# GNSS_GPS_IMU.net
KiCad netlist of a schematic drawn in Altium Designer
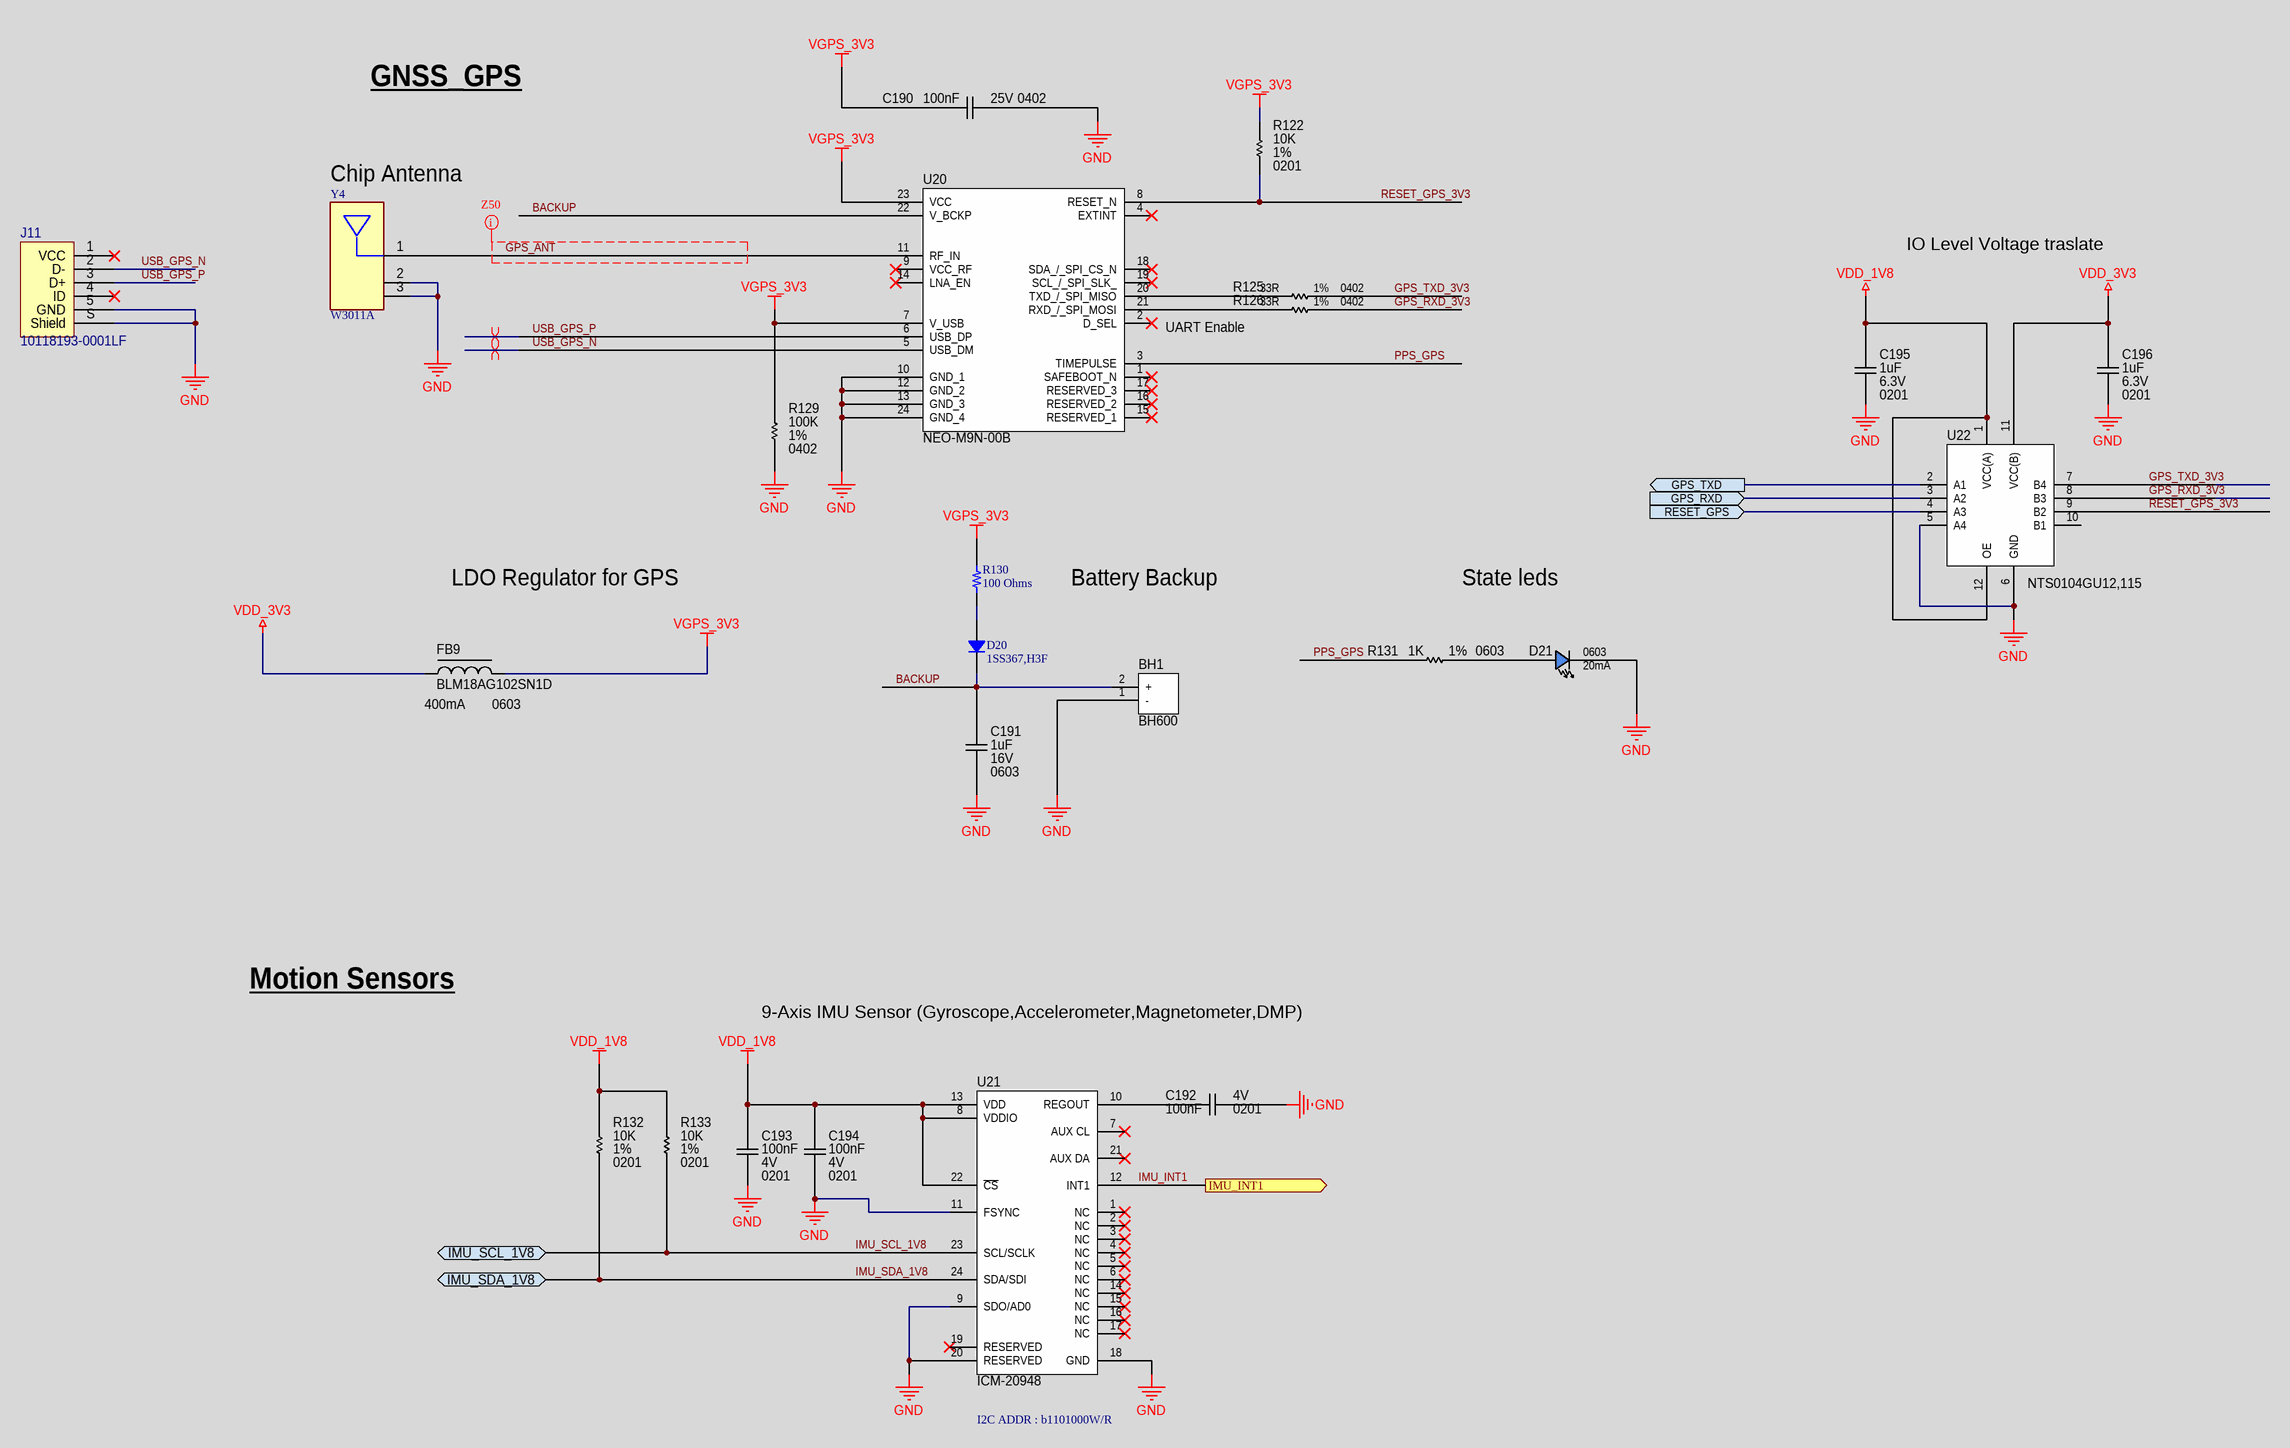
[diagram p0: GNSS_GPS_IMU.SchDoc]

(export (version "E")
  (design (tool "Eeschema 10.0.6"))
  (components
    (comp (ref "BH1")
      (value "BH600")
      (footprint "MECH_BATTERY_HOLDER_BH600")
      (description "Battery Holder 1 Cells Thermoplastic Tray")
      (fields (field (name "MANUFACTURER") "Memory Protection Devices"))
      (libsource (lib "Electronic Devices_LIB") (part "MECH_BATTERY_HOLDER_BH600"))
    )
    (comp (ref "C190")
      (value "CC0402KRX5R8BB104")
      (footprint "CAP_0402_CAPC1005X05N")
      (description "Multilayer Ceramic Capacitor, 0.1 uF, 25 V, ± 10%, X7R, 0402 [1005 Metric]")
      (fields
        (field (name "MANUFACTURER") "Yageo")
        (field (name "TOLERANCE") "10%")
        (field (name "CAPACITANCE") "100nF")
        (field (name "VOLTAGE RATING") "25V")
        (field (name "CASE/PACKAGE") "0402")
      )
      (libsource (lib "Electronic Devices_LIB") (part "CAP_100NF_25V_X7R_0402"))
    )
    (comp (ref "C191")
      (value "CL10A105KO8NNNC")
      (footprint "CAP_0603_CAPC1608X08N")
      (description "CAP CER 1UF 16V X5R 0603")
      (fields
        (field (name "MANUFACTURER") "Samsung")
        (field (name "TOLERANCE") "10%")
        (field (name "VOLTAGE RATING") "16V")
        (field (name "CAPACITANCE") "1uF")
        (field (name "CASE/PACKAGE") "0603")
      )
      (libsource (lib "Electronic Devices_LIB") (part "CAP_1UF_16V_X5R_0603"))
    )
    (comp (ref "C192")
      (value "C0201C104K7PAC7867")
      (footprint "CAP_0201_CAPC0603X03N")
      (description "SMD Comm X5R 0201 (0603Metric) ceramic capacitor 0.024Lx0.012W 0.60mmx0.30mm X5R ±10% 0.1muF")
      (fields
        (field (name "MANUFACTURER") "KEMET")
        (field (name "TOLERANCE") "10%")
        (field (name "VOLTAGE RATING") "4V")
        (field (name "CAPACITANCE") "100nF")
        (field (name "CASE/PACKAGE") "0201")
      )
      (libsource (lib "Electronic Devices_LIB") (part "CAP_100NF_4V_X5R_0201"))
    )
    (comp (ref "C193")
      (value "C0201C104K7PAC7867")
      (footprint "CAP_0201_CAPC0603X03N")
      (description "SMD Comm X5R 0201 (0603Metric) ceramic capacitor 0.024Lx0.012W 0.60mmx0.30mm X5R ±10% 0.1muF")
      (fields
        (field (name "MANUFACTURER") "KEMET")
        (field (name "TOLERANCE") "10%")
        (field (name "VOLTAGE RATING") "4V")
        (field (name "CAPACITANCE") "100nF")
        (field (name "CASE/PACKAGE") "0201")
      )
      (libsource (lib "Electronic Devices_LIB") (part "CAP_100NF_4V_X5R_0201"))
    )
    (comp (ref "C194")
      (value "C0201C104K7PAC7867")
      (footprint "CAP_0201_CAPC0603X03N")
      (description "SMD Comm X5R 0201 (0603Metric) ceramic capacitor 0.024Lx0.012W 0.60mmx0.30mm X5R ±10% 0.1muF")
      (fields
        (field (name "MANUFACTURER") "KEMET")
        (field (name "TOLERANCE") "10%")
        (field (name "VOLTAGE RATING") "4V")
        (field (name "CAPACITANCE") "100nF")
        (field (name "CASE/PACKAGE") "0201")
      )
      (libsource (lib "Electronic Devices_LIB") (part "CAP_100NF_4V_X5R_0201"))
    )
    (comp (ref "C195")
      (value "02016D105MAT2A")
      (footprint "CAP_0201_CAPC0603X03N")
      (description "0201 1 uF 6.3 V ±20 % Tolerance X5R Surface Mount Multilayer Ceramic Capacitor")
      (fields
        (field (name "MANUFACTURER") "Kyocera AVX")
        (field (name "TOLERANCE") "20%")
        (field (name "VOLTAGE RATING (DC)") "6.3V")
        (field (name "CAPACITANCE") "1uF")
        (field (name "CASE/PACKAGE") "0201")
      )
      (libsource (lib "Electronic Devices_LIB") (part "CAP_1UF_6.3V_X5R_0201"))
    )
    (comp (ref "C196")
      (value "02016D105MAT2A")
      (footprint "CAP_0201_CAPC0603X03N")
      (description "0201 1 uF 6.3 V ±20 % Tolerance X5R Surface Mount Multilayer Ceramic Capacitor")
      (fields
        (field (name "MANUFACTURER") "Kyocera AVX")
        (field (name "TOLERANCE") "20%")
        (field (name "VOLTAGE RATING (DC)") "6.3V")
        (field (name "CAPACITANCE") "1uF")
        (field (name "CASE/PACKAGE") "0201")
      )
      (libsource (lib "Electronic Devices_LIB") (part "CAP_1UF_6.3V_X5R_0201"))
    )
    (comp (ref "D20")
      (value "1SS367,H3F")
      (footprint "SOD323")
      (description "DIODE SCHOTTKY 10V 100MA USC")
      (fields (field (name "MANUFACTURER") "Toshiba Semiconductor and Storage"))
      (libsource (lib "Celestial Altium Library - altium_library") (part "Diode"))
    )
    (comp (ref "D21")
      (value "ASCKCB00-NS3T4010302")
      (footprint "LED_0603-BLUE-0.75mm")
      (description "LED Single Chip Blue 467nm 20mA 2-Pin DFN T/R")
      (fields
        (field (name "MANUFACTURER") "Broadcom")
        (field (name "CASE/PACKCAGE") "0603")
        (field (name "TEST CURRENT") "20mA")
      )
      (libsource (lib "Electronic Devices_LIB") (part "LED_DIO_BLUE_20mA_0603_ASCKCB00-NS3T4010302"))
    )
    (comp (ref "FB9")
      (value "BLM18AG102SN1D")
      (footprint "IND_0603_INDC1608X08N")
      (description "Ferrite Beads Multi-Layer 1KOhm 25% 100MHz 450mA 500mOhm DCR 0603 T/R")
      (fields
        (field (name "MANUFACTURER") "Murata")
        (field (name "TOLERANCE") "25%")
        (field (name "MAX DC CURRENT") "400mA")
        (field (name "CASE/PACKAGE") "0603")
      )
      (libsource (lib "Electronic Devices_LIB") (part "IND_FERRITA_1K_450mA_BLM18AG102SN1D"))
    )
    (comp (ref "J11")
      (value "10118193-0001LF")
      (footprint "FCI USB 10118193-0001LF")
      (description "CONN RCPT USB2.0 MICRO B SMD R/A")
      (fields (field (name "MANUFACTURER") "Amphenol ICC (FCI)"))
      (libsource (lib "Celestial Altium Library - altium_library") (part "USB 2.0 Type B Micro"))
    )
    (comp (ref "R122")
      (value "RC0201FR-0710KL")
      (footprint "RES_0201_RESC0603X02N")
      (description "SMD Chip Resistor, 10 kOhm, ± 1%, 50 mW, 0201 [0603 Metric], Thick Film, General Purpose")
      (fields
        (field (name "MANUFACTURER") "Yageo")
        (field (name "TOLERANCE") "1%")
        (field (name "RESISTANCE") "10K")
        (field (name "CASE CODE (IMPERIAL)") "0201")
      )
      (libsource (lib "Electronic Devices_LIB") (part "RES_10K_1/12W_1%_0201"))
    )
    (comp (ref "R125")
      (value "RC0402FR-0733RL")
      (footprint "RES_0402_RESC1005X04N")
      (description "SMD Chip Resistor, 33 Ohm, ± 1%, 62.5 mW, 0402 [1005 Metric], Thick Film, General Purpose")
      (fields
        (field (name "MANUFACTURER") "Yageo")
        (field (name "TOLERANCE") "1%")
        (field (name "RESISTANCE") "33R")
        (field (name "CASE/PACKAGE") "0402")
      )
      (libsource (lib "Electronic Devices_LIB") (part "RES_33R_1%_62.5mW_0402"))
    )
    (comp (ref "R126")
      (value "RC0402FR-0733RL")
      (footprint "RES_0402_RESC1005X04N")
      (description "SMD Chip Resistor, 33 Ohm, ± 1%, 62.5 mW, 0402 [1005 Metric], Thick Film, General Purpose")
      (fields
        (field (name "MANUFACTURER") "Yageo")
        (field (name "TOLERANCE") "1%")
        (field (name "RESISTANCE") "33R")
        (field (name "CASE/PACKAGE") "0402")
      )
      (libsource (lib "Electronic Devices_LIB") (part "RES_33R_1%_62.5mW_0402"))
    )
    (comp (ref "R129")
      (value "RC0402FR-07100KL")
      (footprint "RES_0402_RESC1005X04N")
      (description "SMD Chip Resistor, 100 kOhm, ± 1%, 63 mW, 0402 [1005 Metric], Thick Film, General Purpose")
      (fields
        (field (name "MANUFACTURER") "Yageo")
        (field (name "RESISTANCE") "100K")
        (field (name "TOLERANCE") "1%")
        (field (name "CASE/PACKAGE") "0402")
      )
      (libsource (lib "Electronic Devices_LIB") (part "RES_100K_1%_100mW_0402"))
    )
    (comp (ref "R130")
      (value "100 Ohms")
      (footprint "RES 0402_1005")
      (description "RES 100 OHM 1% 1/16W 0402")
      (fields
        (field (name "PART NUMBER") "RMCF0402FT100R")
        (field (name "MANUFACTURER") "Stackpole Electronics Inc")
      )
      (libsource (lib "Celestial Altium Library - altium_library") (part "Resistor"))
    )
    (comp (ref "R131")
      (value "AC0603FR-101KL")
      (footprint "RES_0603_RESC1608X04N")
      (description "Chip Resistor Automotive Grade Thick Film 0603 1kOhm 1% Paper T/R")
      (fields
        (field (name "MANUFACTURER") "Yageo")
        (field (name "RESISTANCE") "1K")
        (field (name "TOLERANCE") "1%")
        (field (name "CASE/PACKAGE") "0603")
      )
      (libsource (lib "Electronic Devices_LIB") (part "RES_1K_1%_100mW_0603"))
    )
    (comp (ref "R132")
      (value "RC0201FR-0710KL")
      (footprint "RES_0201_RESC0603X02N")
      (description "SMD Chip Resistor, 10 kOhm, ± 1%, 50 mW, 0201 [0603 Metric], Thick Film, General Purpose")
      (fields
        (field (name "MANUFACTURER") "Yageo")
        (field (name "TOLERANCE") "1%")
        (field (name "RESISTANCE") "10K")
        (field (name "CASE CODE (IMPERIAL)") "0201")
      )
      (libsource (lib "Electronic Devices_LIB") (part "RES_10K_1/12W_1%_0201"))
    )
    (comp (ref "R133")
      (value "RC0201FR-0710KL")
      (footprint "RES_0201_RESC0603X02N")
      (description "SMD Chip Resistor, 10 kOhm, ± 1%, 50 mW, 0201 [0603 Metric], Thick Film, General Purpose")
      (fields
        (field (name "MANUFACTURER") "Yageo")
        (field (name "TOLERANCE") "1%")
        (field (name "RESISTANCE") "10K")
        (field (name "CASE CODE (IMPERIAL)") "0201")
      )
      (libsource (lib "Electronic Devices_LIB") (part "RES_10K_1/12W_1%_0201"))
    )
    (comp (ref "U20")
      (value "NEO-M9N-00B")
      (footprint "IC_MODULE_UBLOX_NEOM9N00B")
      (description "GNSS module, Flash, TCXO, SAW, LNA, LCC, 12x16 mm Professional Grade")
      (fields (field (name "MANUFACTURER") "u-blox"))
      (libsource (lib "Electronic Devices_LIB") (part "IC_MODULE_UBLOX_NEO-M9N-00B"))
    )
    (comp (ref "U21")
      (value "ICM-20948")
      (footprint "IC_IMU_TDK_InvenSense_0_IPC_A")
      (description "IMU (Inertial Measurement Unit), 9-Axis, Accelerometer, Gyroscope, Compass")
      (fields (field (name "MANUFACTURER") "TDK"))
      (libsource (lib "Electronic Devices_LIB") (part "IC_IMU_9AXIS_ICM-20948"))
    )
    (comp (ref "U22")
      (value "NTS0104GU12,115")
      (footprint "IC_LEVEL_TRASLATOR_XQFN12_0P4_1P8X2P1")
      (description "NTS0104 Series 50 Mbps Dual Supply 3-ST O-DRN Translating Transceiver- XQFN-12")
      (fields (field (name "MANUFACTURER") "NXP Semiconductors"))
      (libsource (lib "Electronic Devices_LIB") (part "IC_LEVEL_TRASLATOR_NTS0104GU12,115"))
    )
    (comp (ref "Y4")
      (value "W3011A")
      (footprint "FP-W3011A-MFG")
      (description "RF ANT 1.575GHZ CHIP SOLDER SMD")
      (fields
        (field (name "OCTOPART") "https://octopart.com/w3011a-pulse-10684180")
        (field (name "MANUFACTURER") "PulseLarsen Antennas")
      )
      (libsource (lib "Altium Content Vault") (part "6d32a7a60510b62759eb526d3a7a656"))
    )
  )
  (nets
    (net (code "1") (name "/BACKUP") (class "Default")
      (node (ref "BH1") (pin "2") (pinfunction "+_2") (pintype "passive"))
      (node (ref "C191") (pin "2") (pinfunction "2_2") (pintype "passive"))
      (node (ref "D20") (pin "2") (pinfunction "2_2") (pintype "passive"))
      (node (ref "U20") (pin "22") (pinfunction "V_BCKP_22") (pintype "passive"))
    )
    (net (code "2") (name "/GPS_ANT") (class "Default")
      (node (ref "U20") (pin "11") (pinfunction "RF_IN_11") (pintype "passive"))
      (node (ref "Y4") (pin "1") (pinfunction "Feed_1") (pintype "power_in"))
    )
    (net (code "3") (name "/GPS_RXD") (class "Default")
      (node (ref "U22") (pin "3") (pinfunction "A2_3") (pintype "passive"))
    )
    (net (code "4") (name "/GPS_RXD_3V3") (class "Default")
      (node (ref "R126") (pin "2") (pinfunction "2_2") (pintype "passive"))
      (node (ref "U22") (pin "8") (pinfunction "B3_8") (pintype "passive"))
    )
    (net (code "5") (name "/GPS_TXD") (class "Default")
      (node (ref "U22") (pin "2") (pinfunction "A1_2") (pintype "passive"))
    )
    (net (code "6") (name "/GPS_TXD_3V3") (class "Default")
      (node (ref "R125") (pin "2") (pinfunction "2_2") (pintype "passive"))
      (node (ref "U22") (pin "7") (pinfunction "B4_7") (pintype "passive"))
    )
    (net (code "7") (name "/IMU_INT1") (class "Default")
      (node (ref "U21") (pin "12") (pinfunction "INT1_12") (pintype "passive"))
    )
    (net (code "8") (name "/IMU_SCL_1V8") (class "Default")
      (node (ref "R133") (pin "1") (pinfunction "1_1") (pintype "passive"))
      (node (ref "U21") (pin "23") (pinfunction "SCL/SCLK_23") (pintype "passive"))
    )
    (net (code "9") (name "/IMU_SDA_1V8") (class "Default")
      (node (ref "R132") (pin "1") (pinfunction "1_1") (pintype "passive"))
      (node (ref "U21") (pin "24") (pinfunction "SDA/SDI_24") (pintype "passive"))
    )
    (net (code "10") (name "/PPS_GPS") (class "Default")
      (node (ref "R131") (pin "1") (pinfunction "1_1") (pintype "passive"))
      (node (ref "U20") (pin "3") (pinfunction "TIMEPULSE_3") (pintype "passive"))
    )
    (net (code "11") (name "/RESET_GPS") (class "Default")
      (node (ref "U22") (pin "4") (pinfunction "A3_4") (pintype "passive"))
    )
    (net (code "12") (name "/RESET_GPS_3V3") (class "Default")
      (node (ref "R122") (pin "1") (pinfunction "1_1") (pintype "passive"))
      (node (ref "U20") (pin "8") (pinfunction "RESET_N_8") (pintype "passive"))
      (node (ref "U22") (pin "9") (pinfunction "B2_9") (pintype "passive"))
    )
    (net (code "13") (name "/USB_GPS_N") (class "Default")
      (node (ref "J11") (pin "2") (pinfunction "D-_2") (pintype "passive"))
      (node (ref "U20") (pin "5") (pinfunction "USB_DM_5") (pintype "passive"))
    )
    (net (code "14") (name "/USB_GPS_P") (class "Default")
      (node (ref "J11") (pin "3") (pinfunction "D+_3") (pintype "passive"))
      (node (ref "U20") (pin "6") (pinfunction "USB_DP_6") (pintype "passive"))
    )
    (net (code "15") (name "GND") (class "Default")
      (node (ref "BH1") (pin "1") (pinfunction "-_1") (pintype "passive"))
      (node (ref "C190") (pin "2") (pinfunction "2_2") (pintype "passive"))
      (node (ref "C191") (pin "1") (pinfunction "1_1") (pintype "passive"))
      (node (ref "C192") (pin "1") (pinfunction "1_1") (pintype "passive"))
      (node (ref "C193") (pin "1") (pinfunction "1_1") (pintype "passive"))
      (node (ref "C194") (pin "1") (pinfunction "1_1") (pintype "passive"))
      (node (ref "C195") (pin "1") (pinfunction "1_1") (pintype "passive"))
      (node (ref "C196") (pin "1") (pinfunction "1_1") (pintype "passive"))
      (node (ref "D21") (pin "1") (pinfunction "C_1") (pintype "passive"))
      (node (ref "J11") (pin "5") (pinfunction "GND_5") (pintype "passive"))
      (node (ref "J11") (pin "S") (pinfunction "Shield_S") (pintype "passive"))
      (node (ref "R129") (pin "1") (pinfunction "1_1") (pintype "passive"))
      (node (ref "U20") (pin "10") (pinfunction "GND_1_10") (pintype "passive"))
      (node (ref "U20") (pin "12") (pinfunction "GND_2_12") (pintype "passive"))
      (node (ref "U20") (pin "13") (pinfunction "GND_3_13") (pintype "passive"))
      (node (ref "U20") (pin "24") (pinfunction "GND_4_24") (pintype "passive"))
      (node (ref "U21") (pin "11") (pinfunction "FSYNC_11") (pintype "passive"))
      (node (ref "U21") (pin "18") (pinfunction "GND_18") (pintype "power_in"))
      (node (ref "U21") (pin "20") (pinfunction "RESERVED_20") (pintype "passive"))
      (node (ref "U21") (pin "9") (pinfunction "SDO/AD0_9") (pintype "passive"))
      (node (ref "U22") (pin "5") (pinfunction "A4_5") (pintype "passive"))
      (node (ref "U22") (pin "6") (pinfunction "GND_6") (pintype "passive"))
      (node (ref "Y4") (pin "2") (pinfunction "GND_2") (pintype "power_in"))
      (node (ref "Y4") (pin "3") (pinfunction "GND_3") (pintype "power_in"))
    )
    (net (code "16") (name "Net-(D20-Pad1)") (class "Default")
      (node (ref "D20") (pin "1") (pinfunction "1_1") (pintype "passive"))
      (node (ref "R130") (pin "1") (pinfunction "1_1") (pintype "passive"))
    )
    (net (code "17") (name "Net-(D21-A)") (class "Default")
      (node (ref "D21") (pin "2") (pinfunction "A_2") (pintype "passive"))
      (node (ref "R131") (pin "2") (pinfunction "2_2") (pintype "passive"))
    )
    (net (code "18") (name "Net-(U20-RXD_{slash}_SPI_MOSI)") (class "Default")
      (node (ref "R126") (pin "1") (pinfunction "1_1") (pintype "passive"))
      (node (ref "U20") (pin "21") (pinfunction "RXD_/_SPI_MOSI_21") (pintype "passive"))
    )
    (net (code "19") (name "Net-(U20-TXD_{slash}_SPI_MISO)") (class "Default")
      (node (ref "R125") (pin "1") (pinfunction "1_1") (pintype "passive"))
      (node (ref "U20") (pin "20") (pinfunction "TXD_/_SPI_MISO_20") (pintype "passive"))
    )
    (net (code "20") (name "Net-(U21-REGOUT)") (class "Default")
      (node (ref "C192") (pin "2") (pinfunction "2_2") (pintype "passive"))
      (node (ref "U21") (pin "10") (pinfunction "REGOUT_10") (pintype "passive"))
    )
    (net (code "21") (name "VDD_1V8") (class "Default")
      (node (ref "C193") (pin "2") (pinfunction "2_2") (pintype "passive"))
      (node (ref "C194") (pin "2") (pinfunction "2_2") (pintype "passive"))
      (node (ref "C195") (pin "2") (pinfunction "2_2") (pintype "passive"))
      (node (ref "R132") (pin "2") (pinfunction "2_2") (pintype "passive"))
      (node (ref "R133") (pin "2") (pinfunction "2_2") (pintype "passive"))
      (node (ref "U21") (pin "13") (pinfunction "VDD_13") (pintype "power_in"))
      (node (ref "U21") (pin "22") (pinfunction "~{CS}_22") (pintype "passive"))
      (node (ref "U21") (pin "8") (pinfunction "VDDIO_8") (pintype "power_in"))
      (node (ref "U22") (pin "1") (pinfunction "VCC(A)_1") (pintype "passive"))
      (node (ref "U22") (pin "12") (pinfunction "OE_12") (pintype "passive"))
    )
    (net (code "22") (name "VDD_3V3") (class "Default")
      (node (ref "C196") (pin "2") (pinfunction "2_2") (pintype "passive"))
      (node (ref "FB9") (pin "1") (pinfunction "1_1") (pintype "passive"))
      (node (ref "U22") (pin "11") (pinfunction "VCC(B)_11") (pintype "passive"))
    )
    (net (code "23") (name "VGPS_3V3") (class "Default")
      (node (ref "C190") (pin "1") (pinfunction "1_1") (pintype "passive"))
      (node (ref "FB9") (pin "2") (pinfunction "2_2") (pintype "passive"))
      (node (ref "R122") (pin "2") (pinfunction "2_2") (pintype "passive"))
      (node (ref "R129") (pin "2") (pinfunction "2_2") (pintype "passive"))
      (node (ref "R130") (pin "2") (pinfunction "2_2") (pintype "passive"))
      (node (ref "U20") (pin "23") (pinfunction "VCC_23") (pintype "passive"))
      (node (ref "U20") (pin "7") (pinfunction "V_USB_7") (pintype "passive"))
    )
    (net (code "24") (name "unconnected-(J11-ID-Pad4)") (class "Default")
      (node (ref "J11") (pin "4") (pinfunction "ID_4") (pintype "passive+no_connect"))
    )
    (net (code "25") (name "unconnected-(J11-VCC-Pad1)") (class "Default")
      (node (ref "J11") (pin "1") (pinfunction "VCC_1") (pintype "passive+no_connect"))
    )
    (net (code "26") (name "unconnected-(U20-D_SEL-Pad2)") (class "Default")
      (node (ref "U20") (pin "2") (pinfunction "D_SEL_2") (pintype "passive+no_connect"))
    )
    (net (code "27") (name "unconnected-(U20-EXTINT-Pad4)") (class "Default")
      (node (ref "U20") (pin "4") (pinfunction "EXTINT_4") (pintype "passive+no_connect"))
    )
    (net (code "28") (name "unconnected-(U20-LNA_EN-Pad14)") (class "Default")
      (node (ref "U20") (pin "14") (pinfunction "LNA_EN_14") (pintype "passive+no_connect"))
    )
    (net (code "29") (name "unconnected-(U20-RESERVED_1-Pad15)") (class "Default")
      (node (ref "U20") (pin "15") (pinfunction "RESERVED_1_15") (pintype "passive+no_connect"))
    )
    (net (code "30") (name "unconnected-(U20-RESERVED_2-Pad16)") (class "Default")
      (node (ref "U20") (pin "16") (pinfunction "RESERVED_2_16") (pintype "passive+no_connect"))
    )
    (net (code "31") (name "unconnected-(U20-RESERVED_3-Pad17)") (class "Default")
      (node (ref "U20") (pin "17") (pinfunction "RESERVED_3_17") (pintype "passive+no_connect"))
    )
    (net (code "32") (name "unconnected-(U20-SAFEBOOT_N-Pad1)") (class "Default")
      (node (ref "U20") (pin "1") (pinfunction "SAFEBOOT_N_1") (pintype "passive+no_connect"))
    )
    (net (code "33") (name "unconnected-(U20-SCL_{slash}_SPI_SLK_-Pad19)") (class "Default")
      (node (ref "U20") (pin "19") (pinfunction "SCL_/_SPI_SLK__19") (pintype "passive+no_connect"))
    )
    (net (code "34") (name "unconnected-(U20-SDA_{slash}_SPI_CS_N-Pad18)") (class "Default")
      (node (ref "U20") (pin "18") (pinfunction "SDA_/_SPI_CS_N_18") (pintype "passive+no_connect"))
    )
    (net (code "35") (name "unconnected-(U20-VCC_RF-Pad9)") (class "Default")
      (node (ref "U20") (pin "9") (pinfunction "VCC_RF_9") (pintype "passive+no_connect"))
    )
    (net (code "36") (name "unconnected-(U21-AUX_CL-Pad7)") (class "Default")
      (node (ref "U21") (pin "7") (pinfunction "AUX_CL_7") (pintype "passive+no_connect"))
    )
    (net (code "37") (name "unconnected-(U21-AUX_DA-Pad21)") (class "Default")
      (node (ref "U21") (pin "21") (pinfunction "AUX_DA_21") (pintype "passive+no_connect"))
    )
    (net (code "38") (name "unconnected-(U21-NC-Pad1)") (class "Default")
      (node (ref "U21") (pin "1") (pinfunction "NC_1") (pintype "passive+no_connect"))
    )
    (net (code "39") (name "unconnected-(U21-NC-Pad2)") (class "Default")
      (node (ref "U21") (pin "2") (pinfunction "NC_2") (pintype "passive+no_connect"))
    )
    (net (code "40") (name "unconnected-(U21-NC-Pad3)") (class "Default")
      (node (ref "U21") (pin "3") (pinfunction "NC_3") (pintype "passive+no_connect"))
    )
    (net (code "41") (name "unconnected-(U21-NC-Pad4)") (class "Default")
      (node (ref "U21") (pin "4") (pinfunction "NC_4") (pintype "passive+no_connect"))
    )
    (net (code "42") (name "unconnected-(U21-NC-Pad5)") (class "Default")
      (node (ref "U21") (pin "5") (pinfunction "NC_5") (pintype "passive+no_connect"))
    )
    (net (code "43") (name "unconnected-(U21-NC-Pad6)") (class "Default")
      (node (ref "U21") (pin "6") (pinfunction "NC_6") (pintype "passive+no_connect"))
    )
    (net (code "44") (name "unconnected-(U21-NC-Pad14)") (class "Default")
      (node (ref "U21") (pin "14") (pinfunction "NC_14") (pintype "passive+no_connect"))
    )
    (net (code "45") (name "unconnected-(U21-NC-Pad15)") (class "Default")
      (node (ref "U21") (pin "15") (pinfunction "NC_15") (pintype "passive+no_connect"))
    )
    (net (code "46") (name "unconnected-(U21-NC-Pad16)") (class "Default")
      (node (ref "U21") (pin "16") (pinfunction "NC_16") (pintype "passive+no_connect"))
    )
    (net (code "47") (name "unconnected-(U21-NC-Pad17)") (class "Default")
      (node (ref "U21") (pin "17") (pinfunction "NC_17") (pintype "passive+no_connect"))
    )
    (net (code "48") (name "unconnected-(U21-RESERVED-Pad19)") (class "Default")
      (node (ref "U21") (pin "19") (pinfunction "RESERVED_19") (pintype "passive+no_connect"))
    )
    (net (code "49") (name "unconnected-(U22-B1-Pad10)") (class "Default")
      (node (ref "U22") (pin "10") (pinfunction "B1_10") (pintype "passive"))
    )
  )
)
